# schematic_V3_1.net
KiCad netlist of a schematic drawn in EAGLE
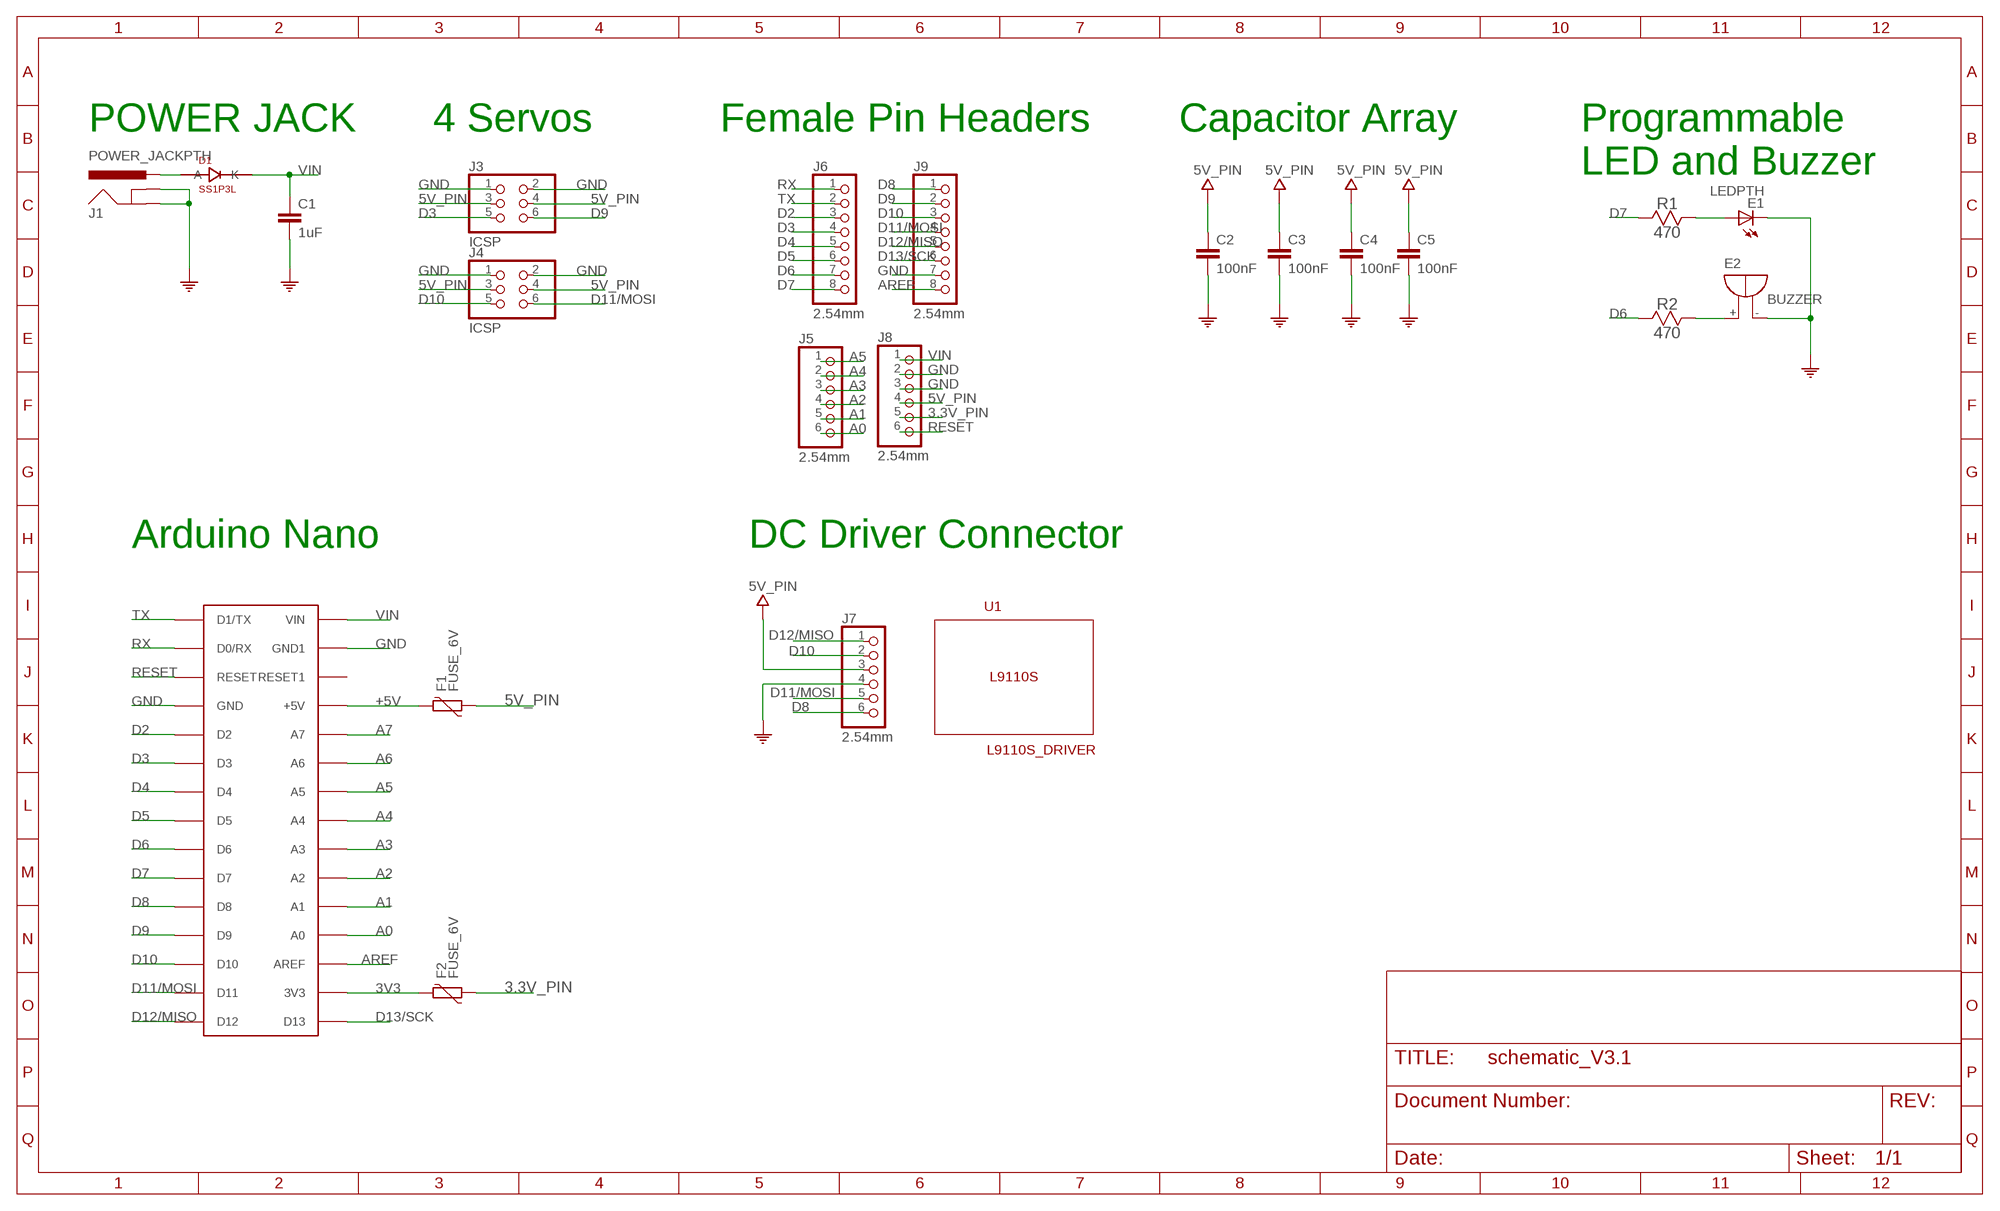
[diagram p0: schematic, sheet 1]

(export (version "E")
  (design (tool "Eeschema 10.0.6"))
  (components
    (comp (ref "C1")
      (value "1uF")
      (footprint "eagle-import:C0603-ROUND")
      (fields (field (name "PARTNO") "CC0603KRX5R8BB105"))
      (libsource (lib "eagle-import") (part "CAPACITOR_1UF_0603"))
    )
    (comp (ref "C2")
      (value "100nF")
      (footprint "eagle-import:C0603-ROUND")
      (fields (field (name "PARTNO") "CC0603ZRY5V9BB104"))
      (libsource (lib "eagle-import") (part "CAPACITOR_100NF_0603"))
    )
    (comp (ref "C3")
      (value "100nF")
      (footprint "eagle-import:C0603-ROUND")
      (fields (field (name "PARTNO") "CC0603ZRY5V9BB104"))
      (libsource (lib "eagle-import") (part "CAPACITOR_100NF_0603"))
    )
    (comp (ref "C4")
      (value "100nF")
      (footprint "eagle-import:C0603-ROUND")
      (fields (field (name "PARTNO") "CC0603ZRY5V9BB104"))
      (libsource (lib "eagle-import") (part "CAPACITOR_100NF_0603"))
    )
    (comp (ref "C5")
      (value "100nF")
      (footprint "eagle-import:C0603-ROUND")
      (fields (field (name "PARTNO") "CC0603ZRY5V9BB104"))
      (libsource (lib "eagle-import") (part "CAPACITOR_100NF_0603"))
    )
    (comp (ref "D1")
      (value "SS1P3L")
      (footprint "eagle-import:DIODI_DO220AAL")
      (fields (field (name "PARTNO") "SS1P3L-M3/84A"))
      (libsource (lib "eagle-import") (part "SCHOTTKY_DIODE"))
    )
    (comp (ref "E1")
      (value "LEDPTH")
      (footprint "eagle-import:LED5MM")
      (libsource (lib "eagle-import") (part "LEDPTH"))
    )
    (comp (ref "E2")
      (value "BUZZER")
      (footprint "eagle-import:BUZZER")
      (libsource (lib "eagle-import") (part "BUZZER"))
    )
    (comp (ref "F1")
      (value "FUSE_6V")
      (footprint "eagle-import:FUSE_0603")
      (fields (field (name "PARTNO") "MF-FSMF050X-2"))
      (libsource (lib "eagle-import") (part "FUSE_6V"))
    )
    (comp (ref "F2")
      (value "FUSE_6V")
      (footprint "eagle-import:FUSE_0603")
      (fields (field (name "PARTNO") "MF-FSMF050X-2"))
      (libsource (lib "eagle-import") (part "FUSE_6V"))
    )
    (comp (ref "J1")
      (value "POWER_JACKPTH")
      (footprint "eagle-import:POWER_JACK_PTH")
      (fields (field (name "PARTNO") "EJ508A"))
      (libsource (lib "eagle-import") (part "POWER_JACKPTH"))
    )
    (comp (ref "J3")
      (value "ICSP")
      (footprint "eagle-import:CONNECTOR_2X3")
      (fields (field (name "PARTNO") "M20-9980346"))
      (libsource (lib "eagle-import") (part "CONNECTOR_2X3"))
    )
    (comp (ref "J4")
      (value "ICSP")
      (footprint "eagle-import:CONNECTOR_2X3")
      (fields (field (name "PARTNO") "M20-9980346"))
      (libsource (lib "eagle-import") (part "CONNECTOR_2X3"))
    )
    (comp (ref "J5")
      (value "2.54mm")
      (footprint "eagle-import:1X06")
      (fields (field (name "PARTNO") "M20-7820646"))
      (libsource (lib "eagle-import") (part "PINHD-1X6"))
    )
    (comp (ref "J6")
      (value "2.54mm")
      (footprint "eagle-import:1X08")
      (fields (field (name "PARTNO") "PPTC081LFBN-RC"))
      (libsource (lib "eagle-import") (part "PINHD-1X8"))
    )
    (comp (ref "J7")
      (value "2.54mm")
      (footprint "eagle-import:1X06")
      (fields (field (name "PARTNO") "M20-7820646"))
      (libsource (lib "eagle-import") (part "PINHD-1X6"))
    )
    (comp (ref "J8")
      (value "2.54mm")
      (footprint "eagle-import:1X06")
      (fields (field (name "PARTNO") "M20-7820646"))
      (libsource (lib "eagle-import") (part "PINHD-1X6"))
    )
    (comp (ref "J9")
      (value "2.54mm")
      (footprint "eagle-import:1X08")
      (fields (field (name "PARTNO") "PPTC081LFBN-RC"))
      (libsource (lib "eagle-import") (part "PINHD-1X8"))
    )
    (comp (ref "R1")
      (value "470")
      (footprint "eagle-import:RESISTOR_PTH")
      (libsource (lib "eagle-import") (part "RESISTOR"))
    )
    (comp (ref "R2")
      (value "470")
      (footprint "eagle-import:RESISTOR_PTH")
      (libsource (lib "eagle-import") (part "RESISTOR"))
    )
    (comp (ref "U$1")
      (value "ARDUINONANO")
      (footprint "eagle-import:PDIP-32")
      (libsource (lib "eagle-import") (part "ARDUINONANO"))
    )
    (comp (ref "U1")
      (value "L9110S_DRIVER")
      (footprint "eagle-import:L9110S_DRIVER")
      (libsource (lib "eagle-import") (part "L9110S_DRIVER"))
    )
  )
  (nets
    (net (code "1") (name "/+5V") (class "Default")
      (node (ref "F1") (pin "2") (pinfunction "2_2") (pintype "passive"))
      (node (ref "U$1") (pin "+5V") (pinfunction "+5V_+5V") (pintype "bidirectional"))
    )
    (net (code "2") (name "/3.3V_PIN") (class "Default")
      (node (ref "F2") (pin "1") (pinfunction "1_1") (pintype "passive"))
      (node (ref "J8") (pin "5") (pinfunction "5_5") (pintype "passive"))
    )
    (net (code "3") (name "/3V3") (class "Default")
      (node (ref "F2") (pin "2") (pinfunction "2_2") (pintype "passive"))
      (node (ref "U$1") (pin "3V3") (pinfunction "3V3_3V3") (pintype "bidirectional"))
    )
    (net (code "4") (name "/A0") (class "Default")
      (node (ref "J5") (pin "6") (pinfunction "6_6") (pintype "passive"))
      (node (ref "U$1") (pin "A7") (pinfunction "A0_A7") (pintype "bidirectional"))
    )
    (net (code "5") (name "/A1") (class "Default")
      (node (ref "J5") (pin "5") (pinfunction "5_5") (pintype "passive"))
      (node (ref "U$1") (pin "A6") (pinfunction "A1_A6") (pintype "bidirectional"))
    )
    (net (code "6") (name "/A2") (class "Default")
      (node (ref "J5") (pin "4") (pinfunction "4_4") (pintype "passive"))
      (node (ref "U$1") (pin "A5") (pinfunction "A2_A5") (pintype "bidirectional"))
    )
    (net (code "7") (name "/A3") (class "Default")
      (node (ref "J5") (pin "3") (pinfunction "3_3") (pintype "passive"))
      (node (ref "U$1") (pin "A4") (pinfunction "A3_A4") (pintype "bidirectional"))
    )
    (net (code "8") (name "/A4") (class "Default")
      (node (ref "J5") (pin "2") (pinfunction "2_2") (pintype "passive"))
      (node (ref "U$1") (pin "A3") (pinfunction "A4_A3") (pintype "bidirectional"))
    )
    (net (code "9") (name "/A5") (class "Default")
      (node (ref "J5") (pin "1") (pinfunction "1_1") (pintype "passive"))
      (node (ref "U$1") (pin "A2") (pinfunction "A5_A2") (pintype "bidirectional"))
    )
    (net (code "10") (name "/A6") (class "Default")
      (node (ref "U$1") (pin "A1") (pinfunction "A6_A1") (pintype "bidirectional"))
    )
    (net (code "11") (name "/A7") (class "Default")
      (node (ref "U$1") (pin "A0") (pinfunction "A7_A0") (pintype "bidirectional"))
    )
    (net (code "12") (name "/AREF") (class "Default")
      (node (ref "J9") (pin "8") (pinfunction "8_8") (pintype "passive"))
      (node (ref "U$1") (pin "AREF") (pinfunction "AREF_AREF") (pintype "bidirectional"))
    )
    (net (code "13") (name "/D2") (class "Default")
      (node (ref "J6") (pin "3") (pinfunction "3_3") (pintype "passive"))
      (node (ref "U$1") (pin "D2") (pinfunction "D2_D2") (pintype "bidirectional"))
    )
    (net (code "14") (name "/D3") (class "Default")
      (node (ref "J3") (pin "5") (pinfunction "5_5") (pintype "passive"))
      (node (ref "J6") (pin "4") (pinfunction "4_4") (pintype "passive"))
      (node (ref "U$1") (pin "D3") (pinfunction "D3_D3") (pintype "bidirectional"))
    )
    (net (code "15") (name "/D4") (class "Default")
      (node (ref "J6") (pin "5") (pinfunction "5_5") (pintype "passive"))
      (node (ref "U$1") (pin "D4") (pinfunction "D4_D4") (pintype "bidirectional"))
    )
    (net (code "16") (name "/D5") (class "Default")
      (node (ref "J6") (pin "6") (pinfunction "6_6") (pintype "passive"))
      (node (ref "U$1") (pin "D5") (pinfunction "D5_D5") (pintype "bidirectional"))
    )
    (net (code "17") (name "/D6") (class "Default")
      (node (ref "J6") (pin "7") (pinfunction "7_7") (pintype "passive"))
      (node (ref "R2") (pin "1") (pinfunction "1_1") (pintype "bidirectional"))
      (node (ref "U$1") (pin "D6") (pinfunction "D6_D6") (pintype "bidirectional"))
    )
    (net (code "18") (name "/D7") (class "Default")
      (node (ref "J6") (pin "8") (pinfunction "8_8") (pintype "passive"))
      (node (ref "R1") (pin "1") (pinfunction "1_1") (pintype "bidirectional"))
      (node (ref "U$1") (pin "D7") (pinfunction "D7_D7") (pintype "bidirectional"))
    )
    (net (code "19") (name "/D8") (class "Default")
      (node (ref "J7") (pin "6") (pinfunction "6_6") (pintype "passive"))
      (node (ref "J9") (pin "1") (pinfunction "1_1") (pintype "passive"))
      (node (ref "U$1") (pin "D8") (pinfunction "D8_D8") (pintype "bidirectional"))
    )
    (net (code "20") (name "/D9") (class "Default")
      (node (ref "J3") (pin "6") (pinfunction "6_6") (pintype "passive"))
      (node (ref "J9") (pin "2") (pinfunction "2_2") (pintype "passive"))
      (node (ref "U$1") (pin "D9") (pinfunction "D9_D9") (pintype "bidirectional"))
    )
    (net (code "21") (name "/D10") (class "Default")
      (node (ref "J4") (pin "5") (pinfunction "5_5") (pintype "passive"))
      (node (ref "J7") (pin "2") (pinfunction "2_2") (pintype "passive"))
      (node (ref "J9") (pin "3") (pinfunction "3_3") (pintype "passive"))
      (node (ref "U$1") (pin "D10") (pinfunction "D10_D10") (pintype "bidirectional"))
    )
    (net (code "22") (name "/D11{slash}MOSI") (class "Default")
      (node (ref "J4") (pin "6") (pinfunction "6_6") (pintype "passive"))
      (node (ref "J7") (pin "5") (pinfunction "5_5") (pintype "passive"))
      (node (ref "J9") (pin "4") (pinfunction "4_4") (pintype "passive"))
      (node (ref "U$1") (pin "D11") (pinfunction "D11_D11") (pintype "bidirectional"))
    )
    (net (code "23") (name "/D12{slash}MISO") (class "Default")
      (node (ref "J7") (pin "1") (pinfunction "1_1") (pintype "passive"))
      (node (ref "J9") (pin "5") (pinfunction "5_5") (pintype "passive"))
      (node (ref "U$1") (pin "D12") (pinfunction "D12_D12") (pintype "bidirectional"))
    )
    (net (code "24") (name "/D13{slash}SCK") (class "Default")
      (node (ref "J9") (pin "6") (pinfunction "6_6") (pintype "passive"))
      (node (ref "U$1") (pin "D13") (pinfunction "D13_D13") (pintype "bidirectional"))
    )
    (net (code "25") (name "/RESET") (class "Default")
      (node (ref "J8") (pin "6") (pinfunction "6_6") (pintype "passive"))
      (node (ref "U$1") (pin "RESET") (pinfunction "RESET_RESET") (pintype "bidirectional"))
    )
    (net (code "26") (name "/RX") (class "Default")
      (node (ref "J6") (pin "1") (pinfunction "1_1") (pintype "passive"))
      (node (ref "U$1") (pin "D0/RX") (pinfunction "D0/RX_D0/RX") (pintype "bidirectional"))
    )
    (net (code "27") (name "/TX") (class "Default")
      (node (ref "J6") (pin "2") (pinfunction "2_2") (pintype "passive"))
      (node (ref "U$1") (pin "D1/TX") (pinfunction "D1/TX_D1/TX") (pintype "bidirectional"))
    )
    (net (code "28") (name "/VIN") (class "Default")
      (node (ref "C1") (pin "1") (pinfunction "1_1") (pintype "passive"))
      (node (ref "D1") (pin "P$1") (pinfunction "K_P$1") (pintype "bidirectional"))
      (node (ref "J8") (pin "1") (pinfunction "1_1") (pintype "passive"))
      (node (ref "U$1") (pin "VIN") (pinfunction "VIN_VIN") (pintype "bidirectional"))
    )
    (net (code "29") (name "5V_PIN") (class "Default")
      (node (ref "C2") (pin "1") (pinfunction "1_1") (pintype "passive"))
      (node (ref "C3") (pin "1") (pinfunction "1_1") (pintype "passive"))
      (node (ref "C4") (pin "1") (pinfunction "1_1") (pintype "passive"))
      (node (ref "C5") (pin "1") (pinfunction "1_1") (pintype "passive"))
      (node (ref "F1") (pin "1") (pinfunction "1_1") (pintype "passive"))
      (node (ref "J3") (pin "3") (pinfunction "3_3") (pintype "passive"))
      (node (ref "J3") (pin "4") (pinfunction "4_4") (pintype "passive"))
      (node (ref "J4") (pin "3") (pinfunction "3_3") (pintype "passive"))
      (node (ref "J4") (pin "4") (pinfunction "4_4") (pintype "passive"))
      (node (ref "J7") (pin "3") (pinfunction "3_3") (pintype "passive"))
      (node (ref "J8") (pin "4") (pinfunction "4_4") (pintype "passive"))
    )
    (net (code "30") (name "GND") (class "Default")
      (node (ref "C1") (pin "2") (pinfunction "2_2") (pintype "passive"))
      (node (ref "C2") (pin "2") (pinfunction "2_2") (pintype "passive"))
      (node (ref "C3") (pin "2") (pinfunction "2_2") (pintype "passive"))
      (node (ref "C4") (pin "2") (pinfunction "2_2") (pintype "passive"))
      (node (ref "C5") (pin "2") (pinfunction "2_2") (pintype "passive"))
      (node (ref "E1") (pin "K") (pinfunction "C_K") (pintype "passive"))
      (node (ref "E2") (pin "-") (pinfunction "-_-") (pintype "passive"))
      (node (ref "J1") (pin "GND") (pinfunction "GND_GND") (pintype "bidirectional"))
      (node (ref "J1") (pin "GNDBREAK") (pinfunction "GNDBREAK_GNDBREAK") (pintype "bidirectional"))
      (node (ref "J3") (pin "1") (pinfunction "1_1") (pintype "passive"))
      (node (ref "J3") (pin "2") (pinfunction "2_2") (pintype "passive"))
      (node (ref "J4") (pin "1") (pinfunction "1_1") (pintype "passive"))
      (node (ref "J4") (pin "2") (pinfunction "2_2") (pintype "passive"))
      (node (ref "J7") (pin "4") (pinfunction "4_4") (pintype "passive"))
      (node (ref "J8") (pin "2") (pinfunction "2_2") (pintype "passive"))
      (node (ref "J8") (pin "3") (pinfunction "3_3") (pintype "passive"))
      (node (ref "J9") (pin "7") (pinfunction "7_7") (pintype "passive"))
      (node (ref "U$1") (pin "GND") (pinfunction "GND_GND") (pintype "bidirectional"))
      (node (ref "U$1") (pin "GND1") (pinfunction "GND1_GND1") (pintype "bidirectional"))
    )
    (net (code "31") (name "Net-(D1-A)") (class "Default")
      (node (ref "D1") (pin "P$2") (pinfunction "A_P$2") (pintype "bidirectional"))
      (node (ref "J1") (pin "PWR") (pinfunction "PWR_PWR") (pintype "bidirectional"))
    )
    (net (code "32") (name "Net-(E1-PadA)") (class "Default")
      (node (ref "E1") (pin "A") (pinfunction "A_A") (pintype "passive"))
      (node (ref "R1") (pin "2") (pinfunction "2_2") (pintype "bidirectional"))
    )
    (net (code "33") (name "Net-(E2-Pad+)") (class "Default")
      (node (ref "E2") (pin "+") (pinfunction "+_+") (pintype "passive"))
      (node (ref "R2") (pin "2") (pinfunction "2_2") (pintype "bidirectional"))
    )
    (net (code "34") (name "unconnected-(U$1-PadRESET1)") (class "Default")
      (node (ref "U$1") (pin "RESET1") (pinfunction "RESET1_RESET1") (pintype "bidirectional"))
    )
  )
)
